# schematic.net
KiCad netlist of a schematic drawn in EAGLE
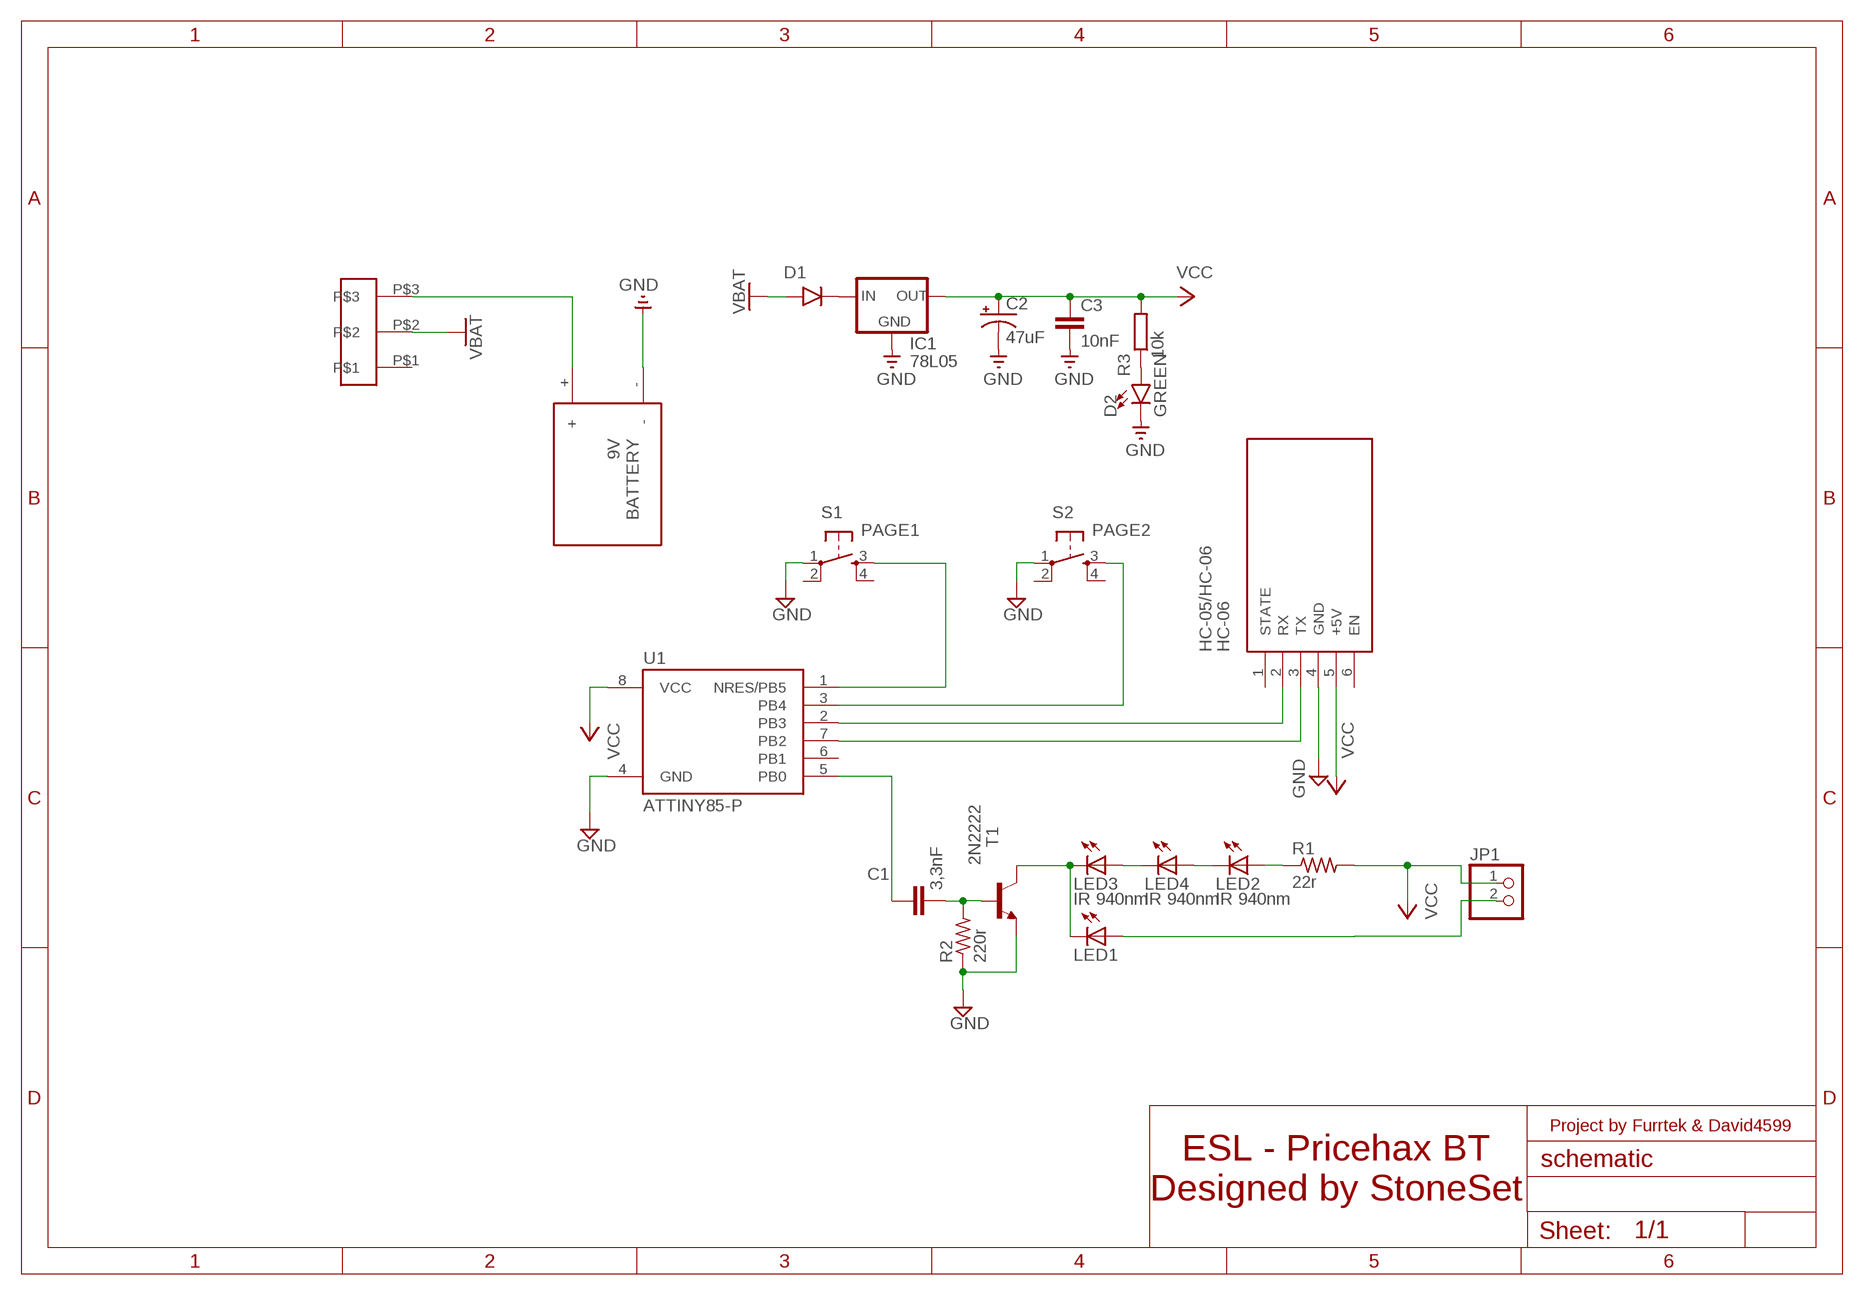
[diagram p0: schematic, sheet 1]

(export (version "E")
  (design (tool "Eeschema 10.0.6"))
  (components
    (comp (ref "C1")
      (value "3,3nF")
      (footprint "eagle-import:C2.5-3")
      (libsource (lib "eagle-import") (part "C2,5-3"))
    )
    (comp (ref "C2")
      (value "47uF")
      (footprint "eagle-import:CPOL-RADIAL-10UF-25V")
      (libsource (lib "eagle-import") (part "CAP_POLPTH2"))
    )
    (comp (ref "C3")
      (value "10nF")
      (footprint "eagle-import:CAP-PTH-10MM")
      (libsource (lib "eagle-import") (part "10NF-PTH-10MM-10000V-1-%"))
    )
    (comp (ref "D1")
      (value "1N4001")
      (footprint "eagle-import:DO41-10")
      (libsource (lib "eagle-import") (part "1N4001"))
    )
    (comp (ref "D2")
      (value "GREEN")
      (footprint "eagle-import:LED_3MM-NS")
      (libsource (lib "eagle-import") (part "LED-3MM-NO_SILK"))
    )
    (comp (ref "HC-05/HC-06")
      (value "HC-06")
      (footprint "eagle-import:WIRELESS-BLUETOOTH-HC-05")
      (libsource (lib "eagle-import") (part "WIRELESS-BLUETOOTH-HC-05"))
    )
    (comp (ref "IC1")
      (value "78L05")
      (footprint "eagle-import:78XXL")
      (libsource (lib "eagle-import") (part "V_REG_78XXSIDE"))
    )
    (comp (ref "JP1")
      (value "PINHD-1X2")
      (footprint "eagle-import:1X02")
      (libsource (lib "eagle-import") (part "PINHD-1X2"))
    )
    (comp (ref "LED1")
      (value "LED5MM")
      (footprint "eagle-import:LED5MM")
      (libsource (lib "eagle-import") (part "adafruit_420_LED5MM"))
    )
    (comp (ref "LED2")
      (value "IR 940nm")
      (footprint "eagle-import:LED5MM")
      (libsource (lib "eagle-import") (part "adafruit_420_LED5MM"))
    )
    (comp (ref "LED3")
      (value "IR 940nm")
      (footprint "eagle-import:LED5MM")
      (libsource (lib "eagle-import") (part "adafruit_420_LED5MM"))
    )
    (comp (ref "LED4")
      (value "IR 940nm")
      (footprint "eagle-import:LED5MM")
      (libsource (lib "eagle-import") (part "adafruit_420_LED5MM"))
    )
    (comp (ref "R1")
      (value "22r")
      (footprint "eagle-import:0204_7")
      (libsource (lib "eagle-import") (part "R-US_0204/7"))
    )
    (comp (ref "R2")
      (value "220r")
      (footprint "eagle-import:0204_7")
      (libsource (lib "eagle-import") (part "R-US_0204/7"))
    )
    (comp (ref "R3")
      (value "10k")
      (footprint "eagle-import:0207_7")
      (libsource (lib "eagle-import") (part "R-EU_0207/7"))
    )
    (comp (ref "S1")
      (value "PAGE1")
      (footprint "eagle-import:DTS-6")
      (libsource (lib "eagle-import") (part "DTS-6"))
    )
    (comp (ref "S2")
      (value "PAGE2")
      (footprint "eagle-import:DTS-6")
      (libsource (lib "eagle-import") (part "DTS-6"))
    )
    (comp (ref "T1")
      (value "2N2222")
      (footprint "eagle-import:TO92-EBC-OVAL")
      (libsource (lib "eagle-import") (part "2N2222"))
    )
    (comp (ref "U$2")
      (value "PACKAGESWITCH")
      (footprint "eagle-import:SLIDESWITCH")
      (libsource (lib "eagle-import") (part "PACKAGESWITCH"))
    )
    (comp (ref "U$3")
      (value "BAT")
      (footprint "eagle-import:BAT")
      (libsource (lib "eagle-import") (part "BAT"))
    )
    (comp (ref "U1")
      (value "ATTINY85-P")
      (footprint "eagle-import:PDIP08_300MIL")
      (libsource (lib "eagle-import") (part "ATTINY85P-"))
    )
  )
  (nets
    (net (code "1") (name "GND") (class "Default")
      (node (ref "C2") (pin "2") (pinfunction "-_2") (pintype "passive"))
      (node (ref "C3") (pin "2") (pinfunction "2_2") (pintype "passive"))
      (node (ref "D2") (pin "K") (pinfunction "C_K") (pintype "passive"))
      (node (ref "HC-05/HC-06") (pin "4") (pinfunction "GND_4") (pintype "power_in"))
      (node (ref "IC1") (pin "GND") (pinfunction "GND_GND") (pintype "input"))
      (node (ref "R2") (pin "1") (pinfunction "1_1") (pintype "passive"))
      (node (ref "S1") (pin "1") (pinfunction "1_1") (pintype "passive"))
      (node (ref "S2") (pin "1") (pinfunction "1_1") (pintype "passive"))
      (node (ref "T1") (pin "E") (pinfunction "E_E") (pintype "passive"))
      (node (ref "U$3") (pin "-") (pinfunction "-_-") (pintype "bidirectional"))
      (node (ref "U1") (pin "4") (pinfunction "GND_4") (pintype "power_in"))
    )
    (net (code "2") (name "Net-(C1-Pad2)") (class "Default")
      (node (ref "C1") (pin "2") (pinfunction "2_2") (pintype "passive"))
      (node (ref "R2") (pin "2") (pinfunction "2_2") (pintype "passive"))
      (node (ref "T1") (pin "B") (pinfunction "B_B") (pintype "passive"))
    )
    (net (code "3") (name "Net-(D1-CATHODE)") (class "Default")
      (node (ref "D1") (pin "C") (pinfunction "CATHODE_C") (pintype "passive"))
      (node (ref "IC1") (pin "IN") (pinfunction "IN_IN") (pintype "input"))
    )
    (net (code "4") (name "Net-(D2-PadA)") (class "Default")
      (node (ref "D2") (pin "A") (pinfunction "A_A") (pintype "passive"))
      (node (ref "R3") (pin "1") (pinfunction "1_1") (pintype "passive"))
    )
    (net (code "5") (name "Net-(HC-05/HC-06-RX)") (class "Default")
      (node (ref "HC-05/HC-06") (pin "2") (pinfunction "RX_2") (pintype "bidirectional"))
      (node (ref "U1") (pin "2") (pinfunction "PB3_2") (pintype "bidirectional"))
    )
    (net (code "6") (name "Net-(HC-05/HC-06-TX)") (class "Default")
      (node (ref "HC-05/HC-06") (pin "3") (pinfunction "TX_3") (pintype "bidirectional"))
      (node (ref "U1") (pin "7") (pinfunction "PB2_7") (pintype "bidirectional"))
    )
    (net (code "7") (name "Net-(JP1-Pad2)") (class "Default")
      (node (ref "JP1") (pin "2") (pinfunction "2_2") (pintype "passive"))
      (node (ref "LED1") (pin "A") (pinfunction "A_A") (pintype "passive"))
    )
    (net (code "8") (name "Net-(LED1-C)") (class "Default")
      (node (ref "LED1") (pin "K") (pinfunction "C_K") (pintype "passive"))
      (node (ref "LED3") (pin "K") (pinfunction "C_K") (pintype "passive"))
      (node (ref "T1") (pin "C") (pinfunction "C_C") (pintype "passive"))
    )
    (net (code "9") (name "Net-(LED2-C)") (class "Default")
      (node (ref "LED2") (pin "K") (pinfunction "C_K") (pintype "passive"))
      (node (ref "LED4") (pin "A") (pinfunction "A_A") (pintype "passive"))
    )
    (net (code "10") (name "Net-(LED2-PadA)") (class "Default")
      (node (ref "LED2") (pin "A") (pinfunction "A_A") (pintype "passive"))
      (node (ref "R1") (pin "1") (pinfunction "1_1") (pintype "passive"))
    )
    (net (code "11") (name "Net-(LED4-C)") (class "Default")
      (node (ref "LED3") (pin "A") (pinfunction "A_A") (pintype "passive"))
      (node (ref "LED4") (pin "K") (pinfunction "C_K") (pintype "passive"))
    )
    (net (code "12") (name "Net-(U$2-PadP$3)") (class "Default")
      (node (ref "U$2") (pin "P$3") (pinfunction "P$3_P$3") (pintype "bidirectional"))
      (node (ref "U$3") (pin "+") (pinfunction "+_+") (pintype "bidirectional"))
    )
    (net (code "13") (name "Net-(U1-NRES{slash}PB5)") (class "Default")
      (node (ref "S1") (pin "3") (pinfunction "3_3") (pintype "passive"))
      (node (ref "U1") (pin "1") (pinfunction "NRES/PB5_1") (pintype "bidirectional"))
    )
    (net (code "14") (name "Net-(U1-PB0)") (class "Default")
      (node (ref "C1") (pin "1") (pinfunction "1_1") (pintype "passive"))
      (node (ref "U1") (pin "5") (pinfunction "PB0_5") (pintype "bidirectional"))
    )
    (net (code "15") (name "Net-(U1-PB4)") (class "Default")
      (node (ref "S2") (pin "3") (pinfunction "3_3") (pintype "passive"))
      (node (ref "U1") (pin "3") (pinfunction "PB4_3") (pintype "bidirectional"))
    )
    (net (code "16") (name "VBAT") (class "Default")
      (node (ref "D1") (pin "A") (pinfunction "ANODE_A") (pintype "passive"))
      (node (ref "U$2") (pin "P$2") (pinfunction "P$2_P$2") (pintype "bidirectional"))
    )
    (net (code "17") (name "VCC") (class "Default")
      (node (ref "C2") (pin "1") (pinfunction "+_1") (pintype "passive"))
      (node (ref "C3") (pin "1") (pinfunction "1_1") (pintype "passive"))
      (node (ref "HC-05/HC-06") (pin "5") (pinfunction "+5V_5") (pintype "power_in"))
      (node (ref "IC1") (pin "OUT") (pinfunction "OUT_OUT") (pintype "output"))
      (node (ref "JP1") (pin "1") (pinfunction "1_1") (pintype "passive"))
      (node (ref "R1") (pin "2") (pinfunction "2_2") (pintype "passive"))
      (node (ref "R3") (pin "2") (pinfunction "2_2") (pintype "passive"))
      (node (ref "U1") (pin "8") (pinfunction "VCC_8") (pintype "power_in"))
    )
    (net (code "18") (name "unconnected-(HC-05/HC-06-EN-Pad6)") (class "Default")
      (node (ref "HC-05/HC-06") (pin "6") (pinfunction "EN_6") (pintype "bidirectional"))
    )
    (net (code "19") (name "unconnected-(HC-05/HC-06-STATE-Pad1)") (class "Default")
      (node (ref "HC-05/HC-06") (pin "1") (pinfunction "STATE_1") (pintype "bidirectional"))
    )
    (net (code "20") (name "unconnected-(S1-Pad2)") (class "Default")
      (node (ref "S1") (pin "2") (pinfunction "2_2") (pintype "passive"))
    )
    (net (code "21") (name "unconnected-(S1-Pad4)") (class "Default")
      (node (ref "S1") (pin "4") (pinfunction "4_4") (pintype "passive"))
    )
    (net (code "22") (name "unconnected-(S2-Pad2)") (class "Default")
      (node (ref "S2") (pin "2") (pinfunction "2_2") (pintype "passive"))
    )
    (net (code "23") (name "unconnected-(S2-Pad4)") (class "Default")
      (node (ref "S2") (pin "4") (pinfunction "4_4") (pintype "passive"))
    )
    (net (code "24") (name "unconnected-(U$2-PadP$1)") (class "Default")
      (node (ref "U$2") (pin "P$1") (pinfunction "P$1_P$1") (pintype "bidirectional"))
    )
    (net (code "25") (name "unconnected-(U1-PB1-Pad6)") (class "Default")
      (node (ref "U1") (pin "6") (pinfunction "PB1_6") (pintype "bidirectional"))
    )
  )
)
